# Sheet1.net
KiCad netlist of a schematic drawn in Altium Designer
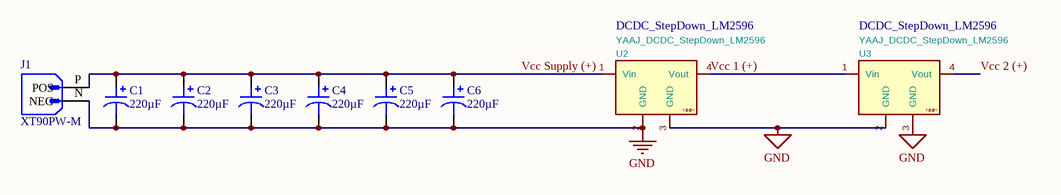
[diagram p0: Sheet1.SchDoc]

(export (version "E")
  (design (tool "Eeschema 10.0.6"))
  (components
    (comp (ref "C1")
      (value "220µF")
      (footprint "CAP TH ALUM ELEC D10.00mm S5.00mm H20.00mm")
      (description "DC Link Capacitor or Bulk Capacitor\r\nCAP ALUM 220UF 20% 63V RADIAL")
      (fields (field (name "PART NUMBER") "UPW1J221MPD") (field (name "MANUFACTURER") "Nichicon"))
      (libsource (lib "Celestial Altium Library - altium_library") (part "Polarised Capacitor"))
    )
    (comp (ref "C2")
      (value "220µF")
      (footprint "CAP TH ALUM ELEC D10.00mm S5.00mm H20.00mm")
      (description "DC Link Capacitor or Bulk Capacitor\r\nCAP ALUM 220UF 20% 63V RADIAL")
      (fields (field (name "PART NUMBER") "UPW1J221MPD") (field (name "MANUFACTURER") "Nichicon"))
      (libsource (lib "Celestial Altium Library - altium_library") (part "Polarised Capacitor"))
    )
    (comp (ref "C3")
      (value "220µF")
      (footprint "CAP TH ALUM ELEC D10.00mm S5.00mm H20.00mm")
      (description "DC Link Capacitor or Bulk Capacitor\r\nCAP ALUM 220UF 20% 63V RADIAL")
      (fields (field (name "PART NUMBER") "UPW1J221MPD") (field (name "MANUFACTURER") "Nichicon"))
      (libsource (lib "Celestial Altium Library - altium_library") (part "Polarised Capacitor"))
    )
    (comp (ref "C4")
      (value "220µF")
      (footprint "CAP TH ALUM ELEC D10.00mm S5.00mm H20.00mm")
      (description "DC Link Capacitor or Bulk Capacitor\r\nCAP ALUM 220UF 20% 63V RADIAL")
      (fields (field (name "PART NUMBER") "UPW1J221MPD") (field (name "MANUFACTURER") "Nichicon"))
      (libsource (lib "Celestial Altium Library - altium_library") (part "Polarised Capacitor"))
    )
    (comp (ref "C5")
      (value "220µF")
      (footprint "CAP TH ALUM ELEC D10.00mm S5.00mm H20.00mm")
      (description "DC Link Capacitor or Bulk Capacitor\r\nCAP ALUM 220UF 20% 63V RADIAL")
      (fields (field (name "PART NUMBER") "UPW1J221MPD") (field (name "MANUFACTURER") "Nichicon"))
      (libsource (lib "Celestial Altium Library - altium_library") (part "Polarised Capacitor"))
    )
    (comp (ref "C6")
      (value "220µF")
      (footprint "CAP TH ALUM ELEC D10.00mm S5.00mm H20.00mm")
      (description "DC Link Capacitor or Bulk Capacitor\r\nCAP ALUM 220UF 20% 63V RADIAL")
      (fields (field (name "PART NUMBER") "UPW1J221MPD") (field (name "MANUFACTURER") "Nichicon"))
      (libsource (lib "Celestial Altium Library - altium_library") (part "Polarised Capacitor"))
    )
    (comp (ref "J1")
      (value "XT90PW-M")
      (footprint "AMASS_XT90PW-M")
      (description "LiPo Battery 6s\r\nySocket; DC supply; XT90; male; PIN: 2; on PCBs; THT; Colour: yellow")
      (fields (field (name "MF") "AMASS"))
      (libsource (lib "XT90PW-M") (part "XT90PW-M"))
    )
    (comp (ref "U2")
      (value "DCDC_StepDown_LM2596")
      (footprint "YAAJ_DCDC_StepDown_LM2596")
      (description "Buck Converver 15V")
      (fields (field (name "ALTIUM_VALUE") "YAAJ_DCDC_StepDown_LM2596"))
      (libsource (lib "DCDC_StepDown_LM2596") (part "YAAJ_DCDC_StepDown_LM2596"))
    )
    (comp (ref "U3")
      (value "DCDC_StepDown_LM2596")
      (footprint "YAAJ_DCDC_StepDown_LM2596")
      (description "Buck Converver 5V")
      (fields (field (name "ALTIUM_VALUE") "YAAJ_DCDC_StepDown_LM2596"))
      (libsource (lib "DCDC_StepDown_LM2596") (part "YAAJ_DCDC_StepDown_LM2596"))
    )
  )
  (nets
    (net (code "1") (name "/Vcc 1 (+)") (class "Default")
      (node (ref "U2") (pin "4") (pinfunction "Vout_4") (pintype "passive"))
      (node (ref "U3") (pin "1") (pinfunction "Vin_1") (pintype "passive"))
    )
    (net (code "2") (name "/Vcc 2 (+)") (class "Default")
      (node (ref "U3") (pin "4") (pinfunction "Vout_4") (pintype "passive"))
    )
    (net (code "3") (name "/Vcc Supply (+)") (class "Default")
      (node (ref "C1") (pin "1") (pinfunction "1_1") (pintype "passive"))
      (node (ref "C2") (pin "1") (pinfunction "1_1") (pintype "passive"))
      (node (ref "C3") (pin "1") (pinfunction "1_1") (pintype "passive"))
      (node (ref "C4") (pin "1") (pinfunction "1_1") (pintype "passive"))
      (node (ref "C5") (pin "1") (pinfunction "1_1") (pintype "passive"))
      (node (ref "C6") (pin "1") (pinfunction "1_1") (pintype "passive"))
      (node (ref "J1") (pin "P") (pinfunction "POS_P") (pintype "passive"))
      (node (ref "U2") (pin "1") (pinfunction "Vin_1") (pintype "passive"))
    )
    (net (code "4") (name "GND") (class "Default")
      (node (ref "C1") (pin "2") (pinfunction "2_2") (pintype "passive"))
      (node (ref "C2") (pin "2") (pinfunction "2_2") (pintype "passive"))
      (node (ref "C3") (pin "2") (pinfunction "2_2") (pintype "passive"))
      (node (ref "C4") (pin "2") (pinfunction "2_2") (pintype "passive"))
      (node (ref "C5") (pin "2") (pinfunction "2_2") (pintype "passive"))
      (node (ref "C6") (pin "2") (pinfunction "2_2") (pintype "passive"))
      (node (ref "J1") (pin "N") (pinfunction "NEG_N") (pintype "passive"))
      (node (ref "U2") (pin "2") (pinfunction "GND_2") (pintype "passive"))
      (node (ref "U2") (pin "3") (pinfunction "GND_3") (pintype "passive"))
      (node (ref "U3") (pin "2") (pinfunction "GND_2") (pintype "passive"))
      (node (ref "U3") (pin "3") (pinfunction "GND_3") (pintype "passive"))
    )
  )
)
